# SCH_04_Chest_Lead_Amplifier.net
KiCad netlist of a schematic drawn in Altium Designer
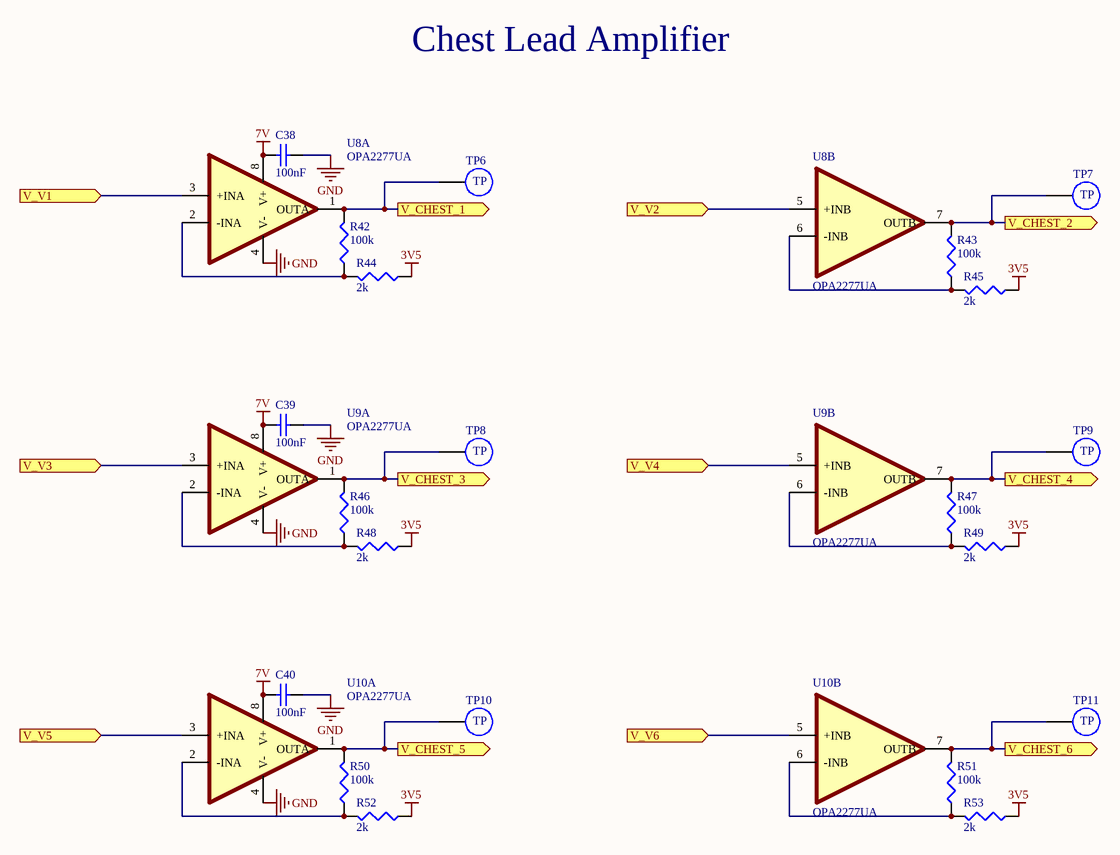
[diagram p0: SCH_04_Chest_Lead_Amplifier.SchDoc]

(export (version "E")
  (design (tool "Eeschema 10.0.6"))
  (components
    (comp (ref "C38")
      (value "100nF")
      (footprint "WCAP-CSGP_0603_L1.6W0.8H0.8_Reflow")
      (description "WCAP-CSGP Multilayer Ceramic Chip Capacitor, General Purpose, size 0603, X7R, 100nF, 50VDC")
      (fields
        (field (name "MANUFACTURER PART NUMBER") "885012206095")
        (field (name "MANUFACTURER") "Wurth Elektronik")
      )
      (libsource (lib "Altium_WCAP-CSGP (rev24b)") (part "885012206095"))
    )
    (comp (ref "C39")
      (value "100nF")
      (footprint "WCAP-CSGP_0603_L1.6W0.8H0.8_Reflow")
      (description "WCAP-CSGP Multilayer Ceramic Chip Capacitor, General Purpose, size 0603, X7R, 100nF, 50VDC")
      (fields
        (field (name "MANUFACTURER PART NUMBER") "885012206095")
        (field (name "MANUFACTURER") "Wurth Elektronik")
      )
      (libsource (lib "Altium_WCAP-CSGP (rev24b)") (part "885012206095"))
    )
    (comp (ref "C40")
      (value "100nF")
      (footprint "WCAP-CSGP_0603_L1.6W0.8H0.8_Reflow")
      (description "WCAP-CSGP Multilayer Ceramic Chip Capacitor, General Purpose, size 0603, X7R, 100nF, 50VDC")
      (fields
        (field (name "MANUFACTURER PART NUMBER") "885012206095")
        (field (name "MANUFACTURER") "Wurth Elektronik")
      )
      (libsource (lib "Altium_WCAP-CSGP (rev24b)") (part "885012206095"))
    )
    (comp (ref "R42")
      (value "100k")
      (footprint "WRIS-PSMB_0603_L1.6W0.8H0.35")
      (description "WRIS-PSMB Metal Plate Resistor, SMT, size 0603, 0.33W, 5mΩ, +/-1%")
      (fields
        (field (name "MANUFACTURER PART NUMBER") "580060716001")
        (field (name "MANUFACTURER") "Wurth Elektronik")
      )
      (libsource (lib "Altium_WRIS-PSMB (rev22a)") (part "580060716001"))
    )
    (comp (ref "R43")
      (value "100k")
      (footprint "WRIS-PSMB_0603_L1.6W0.8H0.35")
      (description "WRIS-PSMB Metal Plate Resistor, SMT, size 0603, 0.33W, 5mΩ, +/-1%")
      (fields
        (field (name "MANUFACTURER PART NUMBER") "580060716001")
        (field (name "MANUFACTURER") "Wurth Elektronik")
      )
      (libsource (lib "Altium_WRIS-PSMB (rev22a)") (part "580060716001"))
    )
    (comp (ref "R44")
      (value "2k")
      (footprint "WRIS-PSMB_0603_L1.6W0.8H0.35")
      (description "WRIS-PSMB Metal Plate Resistor, SMT, size 0603, 0.33W, 5mΩ, +/-1%")
      (fields
        (field (name "MANUFACTURER PART NUMBER") "580060716001")
        (field (name "MANUFACTURER") "Wurth Elektronik")
      )
      (libsource (lib "Altium_WRIS-PSMB (rev22a)") (part "580060716001"))
    )
    (comp (ref "R45")
      (value "2k")
      (footprint "WRIS-PSMB_0603_L1.6W0.8H0.35")
      (description "WRIS-PSMB Metal Plate Resistor, SMT, size 0603, 0.33W, 5mΩ, +/-1%")
      (fields
        (field (name "MANUFACTURER PART NUMBER") "580060716001")
        (field (name "MANUFACTURER") "Wurth Elektronik")
      )
      (libsource (lib "Altium_WRIS-PSMB (rev22a)") (part "580060716001"))
    )
    (comp (ref "R46")
      (value "100k")
      (footprint "WRIS-PSMB_0603_L1.6W0.8H0.35")
      (description "WRIS-PSMB Metal Plate Resistor, SMT, size 0603, 0.33W, 5mΩ, +/-1%")
      (fields
        (field (name "MANUFACTURER PART NUMBER") "580060716001")
        (field (name "MANUFACTURER") "Wurth Elektronik")
      )
      (libsource (lib "Altium_WRIS-PSMB (rev22a)") (part "580060716001"))
    )
    (comp (ref "R47")
      (value "100k")
      (footprint "WRIS-PSMB_0603_L1.6W0.8H0.35")
      (description "WRIS-PSMB Metal Plate Resistor, SMT, size 0603, 0.33W, 5mΩ, +/-1%")
      (fields
        (field (name "MANUFACTURER PART NUMBER") "580060716001")
        (field (name "MANUFACTURER") "Wurth Elektronik")
      )
      (libsource (lib "Altium_WRIS-PSMB (rev22a)") (part "580060716001"))
    )
    (comp (ref "R48")
      (value "2k")
      (footprint "WRIS-PSMB_0603_L1.6W0.8H0.35")
      (description "WRIS-PSMB Metal Plate Resistor, SMT, size 0603, 0.33W, 5mΩ, +/-1%")
      (fields
        (field (name "MANUFACTURER PART NUMBER") "580060716001")
        (field (name "MANUFACTURER") "Wurth Elektronik")
      )
      (libsource (lib "Altium_WRIS-PSMB (rev22a)") (part "580060716001"))
    )
    (comp (ref "R49")
      (value "2k")
      (footprint "WRIS-PSMB_0603_L1.6W0.8H0.35")
      (description "WRIS-PSMB Metal Plate Resistor, SMT, size 0603, 0.33W, 5mΩ, +/-1%")
      (fields
        (field (name "MANUFACTURER PART NUMBER") "580060716001")
        (field (name "MANUFACTURER") "Wurth Elektronik")
      )
      (libsource (lib "Altium_WRIS-PSMB (rev22a)") (part "580060716001"))
    )
    (comp (ref "R50")
      (value "100k")
      (footprint "WRIS-PSMB_0603_L1.6W0.8H0.35")
      (description "WRIS-PSMB Metal Plate Resistor, SMT, size 0603, 0.33W, 5mΩ, +/-1%")
      (fields
        (field (name "MANUFACTURER PART NUMBER") "580060716001")
        (field (name "MANUFACTURER") "Wurth Elektronik")
      )
      (libsource (lib "Altium_WRIS-PSMB (rev22a)") (part "580060716001"))
    )
    (comp (ref "R51")
      (value "100k")
      (footprint "WRIS-PSMB_0603_L1.6W0.8H0.35")
      (description "WRIS-PSMB Metal Plate Resistor, SMT, size 0603, 0.33W, 5mΩ, +/-1%")
      (fields
        (field (name "MANUFACTURER PART NUMBER") "580060716001")
        (field (name "MANUFACTURER") "Wurth Elektronik")
      )
      (libsource (lib "Altium_WRIS-PSMB (rev22a)") (part "580060716001"))
    )
    (comp (ref "R52")
      (value "2k")
      (footprint "WRIS-PSMB_0603_L1.6W0.8H0.35")
      (description "WRIS-PSMB Metal Plate Resistor, SMT, size 0603, 0.33W, 5mΩ, +/-1%")
      (fields
        (field (name "MANUFACTURER PART NUMBER") "580060716001")
        (field (name "MANUFACTURER") "Wurth Elektronik")
      )
      (libsource (lib "Altium_WRIS-PSMB (rev22a)") (part "580060716001"))
    )
    (comp (ref "R53")
      (value "2k")
      (footprint "WRIS-PSMB_0603_L1.6W0.8H0.35")
      (description "WRIS-PSMB Metal Plate Resistor, SMT, size 0603, 0.33W, 5mΩ, +/-1%")
      (fields
        (field (name "MANUFACTURER PART NUMBER") "580060716001")
        (field (name "MANUFACTURER") "Wurth Elektronik")
      )
      (libsource (lib "Altium_WRIS-PSMB (rev22a)") (part "580060716001"))
    )
    (comp (ref "TP6")
      (value "Pad_Test_Point")
      (footprint "Pad_Test_Point")
      (libsource (lib "Test_Point") (part "Pad_Test_Point"))
    )
    (comp (ref "TP7")
      (value "Pad_Test_Point")
      (footprint "Pad_Test_Point")
      (libsource (lib "Test_Point") (part "Pad_Test_Point"))
    )
    (comp (ref "TP8")
      (value "Pad_Test_Point")
      (footprint "Pad_Test_Point")
      (libsource (lib "Test_Point") (part "Pad_Test_Point"))
    )
    (comp (ref "TP9")
      (value "Pad_Test_Point")
      (footprint "Pad_Test_Point")
      (libsource (lib "Test_Point") (part "Pad_Test_Point"))
    )
    (comp (ref "TP10")
      (value "Pad_Test_Point")
      (footprint "Pad_Test_Point")
      (libsource (lib "Test_Point") (part "Pad_Test_Point"))
    )
    (comp (ref "TP11")
      (value "Pad_Test_Point")
      (footprint "Pad_Test_Point")
      (libsource (lib "Test_Point") (part "Pad_Test_Point"))
    )
    (comp (ref "U8")
      (value "OPA2277UA")
      (footprint "SOIC127P599X175-8N")
      (fields (field (name "MP") "OPA2227UA"))
      (libsource (lib "OPA2277") (part "OPA2277UA"))
    )
    (comp (ref "U9")
      (value "OPA2277UA")
      (footprint "SOIC127P599X175-8N")
      (fields (field (name "MP") "OPA2227UA"))
      (libsource (lib "OPA2277") (part "OPA2277UA"))
    )
    (comp (ref "U10")
      (value "OPA2277UA")
      (footprint "SOIC127P599X175-8N")
      (fields (field (name "MP") "OPA2227UA"))
      (libsource (lib "OPA2277") (part "OPA2277UA"))
    )
  )
  (nets
    (net (code "1") (name "/V_CHEST_1") (class "Default")
      (node (ref "R42") (pin "2") (pinfunction "2_2") (pintype "passive"))
      (node (ref "TP6") (pin "1") (pinfunction "1_1") (pintype "passive"))
      (node (ref "U8") (pin "1") (pinfunction "OUTA_1") (pintype "passive"))
    )
    (net (code "2") (name "/V_CHEST_2") (class "Default")
      (node (ref "R43") (pin "2") (pinfunction "2_2") (pintype "passive"))
      (node (ref "TP7") (pin "1") (pinfunction "1_1") (pintype "passive"))
      (node (ref "U8") (pin "7") (pinfunction "OUTB_7") (pintype "passive"))
    )
    (net (code "3") (name "/V_CHEST_3") (class "Default")
      (node (ref "R46") (pin "2") (pinfunction "2_2") (pintype "passive"))
      (node (ref "TP8") (pin "1") (pinfunction "1_1") (pintype "passive"))
      (node (ref "U9") (pin "1") (pinfunction "OUTA_1") (pintype "passive"))
    )
    (net (code "4") (name "/V_CHEST_4") (class "Default")
      (node (ref "R47") (pin "2") (pinfunction "2_2") (pintype "passive"))
      (node (ref "TP9") (pin "1") (pinfunction "1_1") (pintype "passive"))
      (node (ref "U9") (pin "7") (pinfunction "OUTB_7") (pintype "passive"))
    )
    (net (code "5") (name "/V_CHEST_5") (class "Default")
      (node (ref "R50") (pin "2") (pinfunction "2_2") (pintype "passive"))
      (node (ref "TP10") (pin "1") (pinfunction "1_1") (pintype "passive"))
      (node (ref "U10") (pin "1") (pinfunction "OUTA_1") (pintype "passive"))
    )
    (net (code "6") (name "/V_CHEST_6") (class "Default")
      (node (ref "R51") (pin "2") (pinfunction "2_2") (pintype "passive"))
      (node (ref "TP11") (pin "1") (pinfunction "1_1") (pintype "passive"))
      (node (ref "U10") (pin "7") (pinfunction "OUTB_7") (pintype "passive"))
    )
    (net (code "7") (name "/V_V1") (class "Default")
      (node (ref "U8") (pin "3") (pinfunction "+INA_3") (pintype "passive"))
    )
    (net (code "8") (name "/V_V2") (class "Default")
      (node (ref "U8") (pin "5") (pinfunction "+INB_5") (pintype "passive"))
    )
    (net (code "9") (name "/V_V3") (class "Default")
      (node (ref "U9") (pin "3") (pinfunction "+INA_3") (pintype "passive"))
    )
    (net (code "10") (name "/V_V4") (class "Default")
      (node (ref "U9") (pin "5") (pinfunction "+INB_5") (pintype "passive"))
    )
    (net (code "11") (name "/V_V5") (class "Default")
      (node (ref "U10") (pin "3") (pinfunction "+INA_3") (pintype "passive"))
    )
    (net (code "12") (name "/V_V6") (class "Default")
      (node (ref "U10") (pin "5") (pinfunction "+INB_5") (pintype "passive"))
    )
    (net (code "13") (name "3V5") (class "Default")
      (node (ref "R44") (pin "1") (pinfunction "1_1") (pintype "passive"))
      (node (ref "R45") (pin "1") (pinfunction "1_1") (pintype "passive"))
      (node (ref "R48") (pin "1") (pinfunction "1_1") (pintype "passive"))
      (node (ref "R49") (pin "1") (pinfunction "1_1") (pintype "passive"))
      (node (ref "R52") (pin "1") (pinfunction "1_1") (pintype "passive"))
      (node (ref "R53") (pin "1") (pinfunction "1_1") (pintype "passive"))
    )
    (net (code "14") (name "7V") (class "Default")
      (node (ref "C38") (pin "2") (pinfunction "2_2") (pintype "passive"))
      (node (ref "C39") (pin "2") (pinfunction "2_2") (pintype "passive"))
      (node (ref "C40") (pin "2") (pinfunction "2_2") (pintype "passive"))
      (node (ref "U10") (pin "8") (pinfunction "V+_8") (pintype "power_in"))
      (node (ref "U8") (pin "8") (pinfunction "V+_8") (pintype "power_in"))
      (node (ref "U9") (pin "8") (pinfunction "V+_8") (pintype "power_in"))
    )
    (net (code "15") (name "GND") (class "Default")
      (node (ref "C38") (pin "1") (pinfunction "1_1") (pintype "passive"))
      (node (ref "C39") (pin "1") (pinfunction "1_1") (pintype "passive"))
      (node (ref "C40") (pin "1") (pinfunction "1_1") (pintype "passive"))
      (node (ref "U10") (pin "4") (pinfunction "V-_4") (pintype "power_in"))
      (node (ref "U8") (pin "4") (pinfunction "V-_4") (pintype "power_in"))
      (node (ref "U9") (pin "4") (pinfunction "V-_4") (pintype "power_in"))
    )
    (net (code "16") (name "Net-(U8A--INA)") (class "Default")
      (node (ref "R42") (pin "1") (pinfunction "1_1") (pintype "passive"))
      (node (ref "R44") (pin "2") (pinfunction "2_2") (pintype "passive"))
      (node (ref "U8") (pin "2") (pinfunction "-INA_2") (pintype "passive"))
    )
    (net (code "17") (name "Net-(U8B--INB)") (class "Default")
      (node (ref "R43") (pin "1") (pinfunction "1_1") (pintype "passive"))
      (node (ref "R45") (pin "2") (pinfunction "2_2") (pintype "passive"))
      (node (ref "U8") (pin "6") (pinfunction "-INB_6") (pintype "passive"))
    )
    (net (code "18") (name "Net-(U9A--INA)") (class "Default")
      (node (ref "R46") (pin "1") (pinfunction "1_1") (pintype "passive"))
      (node (ref "R48") (pin "2") (pinfunction "2_2") (pintype "passive"))
      (node (ref "U9") (pin "2") (pinfunction "-INA_2") (pintype "passive"))
    )
    (net (code "19") (name "Net-(U9B--INB)") (class "Default")
      (node (ref "R47") (pin "1") (pinfunction "1_1") (pintype "passive"))
      (node (ref "R49") (pin "2") (pinfunction "2_2") (pintype "passive"))
      (node (ref "U9") (pin "6") (pinfunction "-INB_6") (pintype "passive"))
    )
    (net (code "20") (name "Net-(U10A--INA)") (class "Default")
      (node (ref "R50") (pin "1") (pinfunction "1_1") (pintype "passive"))
      (node (ref "R52") (pin "2") (pinfunction "2_2") (pintype "passive"))
      (node (ref "U10") (pin "2") (pinfunction "-INA_2") (pintype "passive"))
    )
    (net (code "21") (name "Net-(U10B--INB)") (class "Default")
      (node (ref "R51") (pin "1") (pinfunction "1_1") (pintype "passive"))
      (node (ref "R53") (pin "2") (pinfunction "2_2") (pintype "passive"))
      (node (ref "U10") (pin "6") (pinfunction "-INB_6") (pintype "passive"))
    )
  )
)
